# Main_schem.net
KiCad netlist of a schematic drawn in Altium Designer
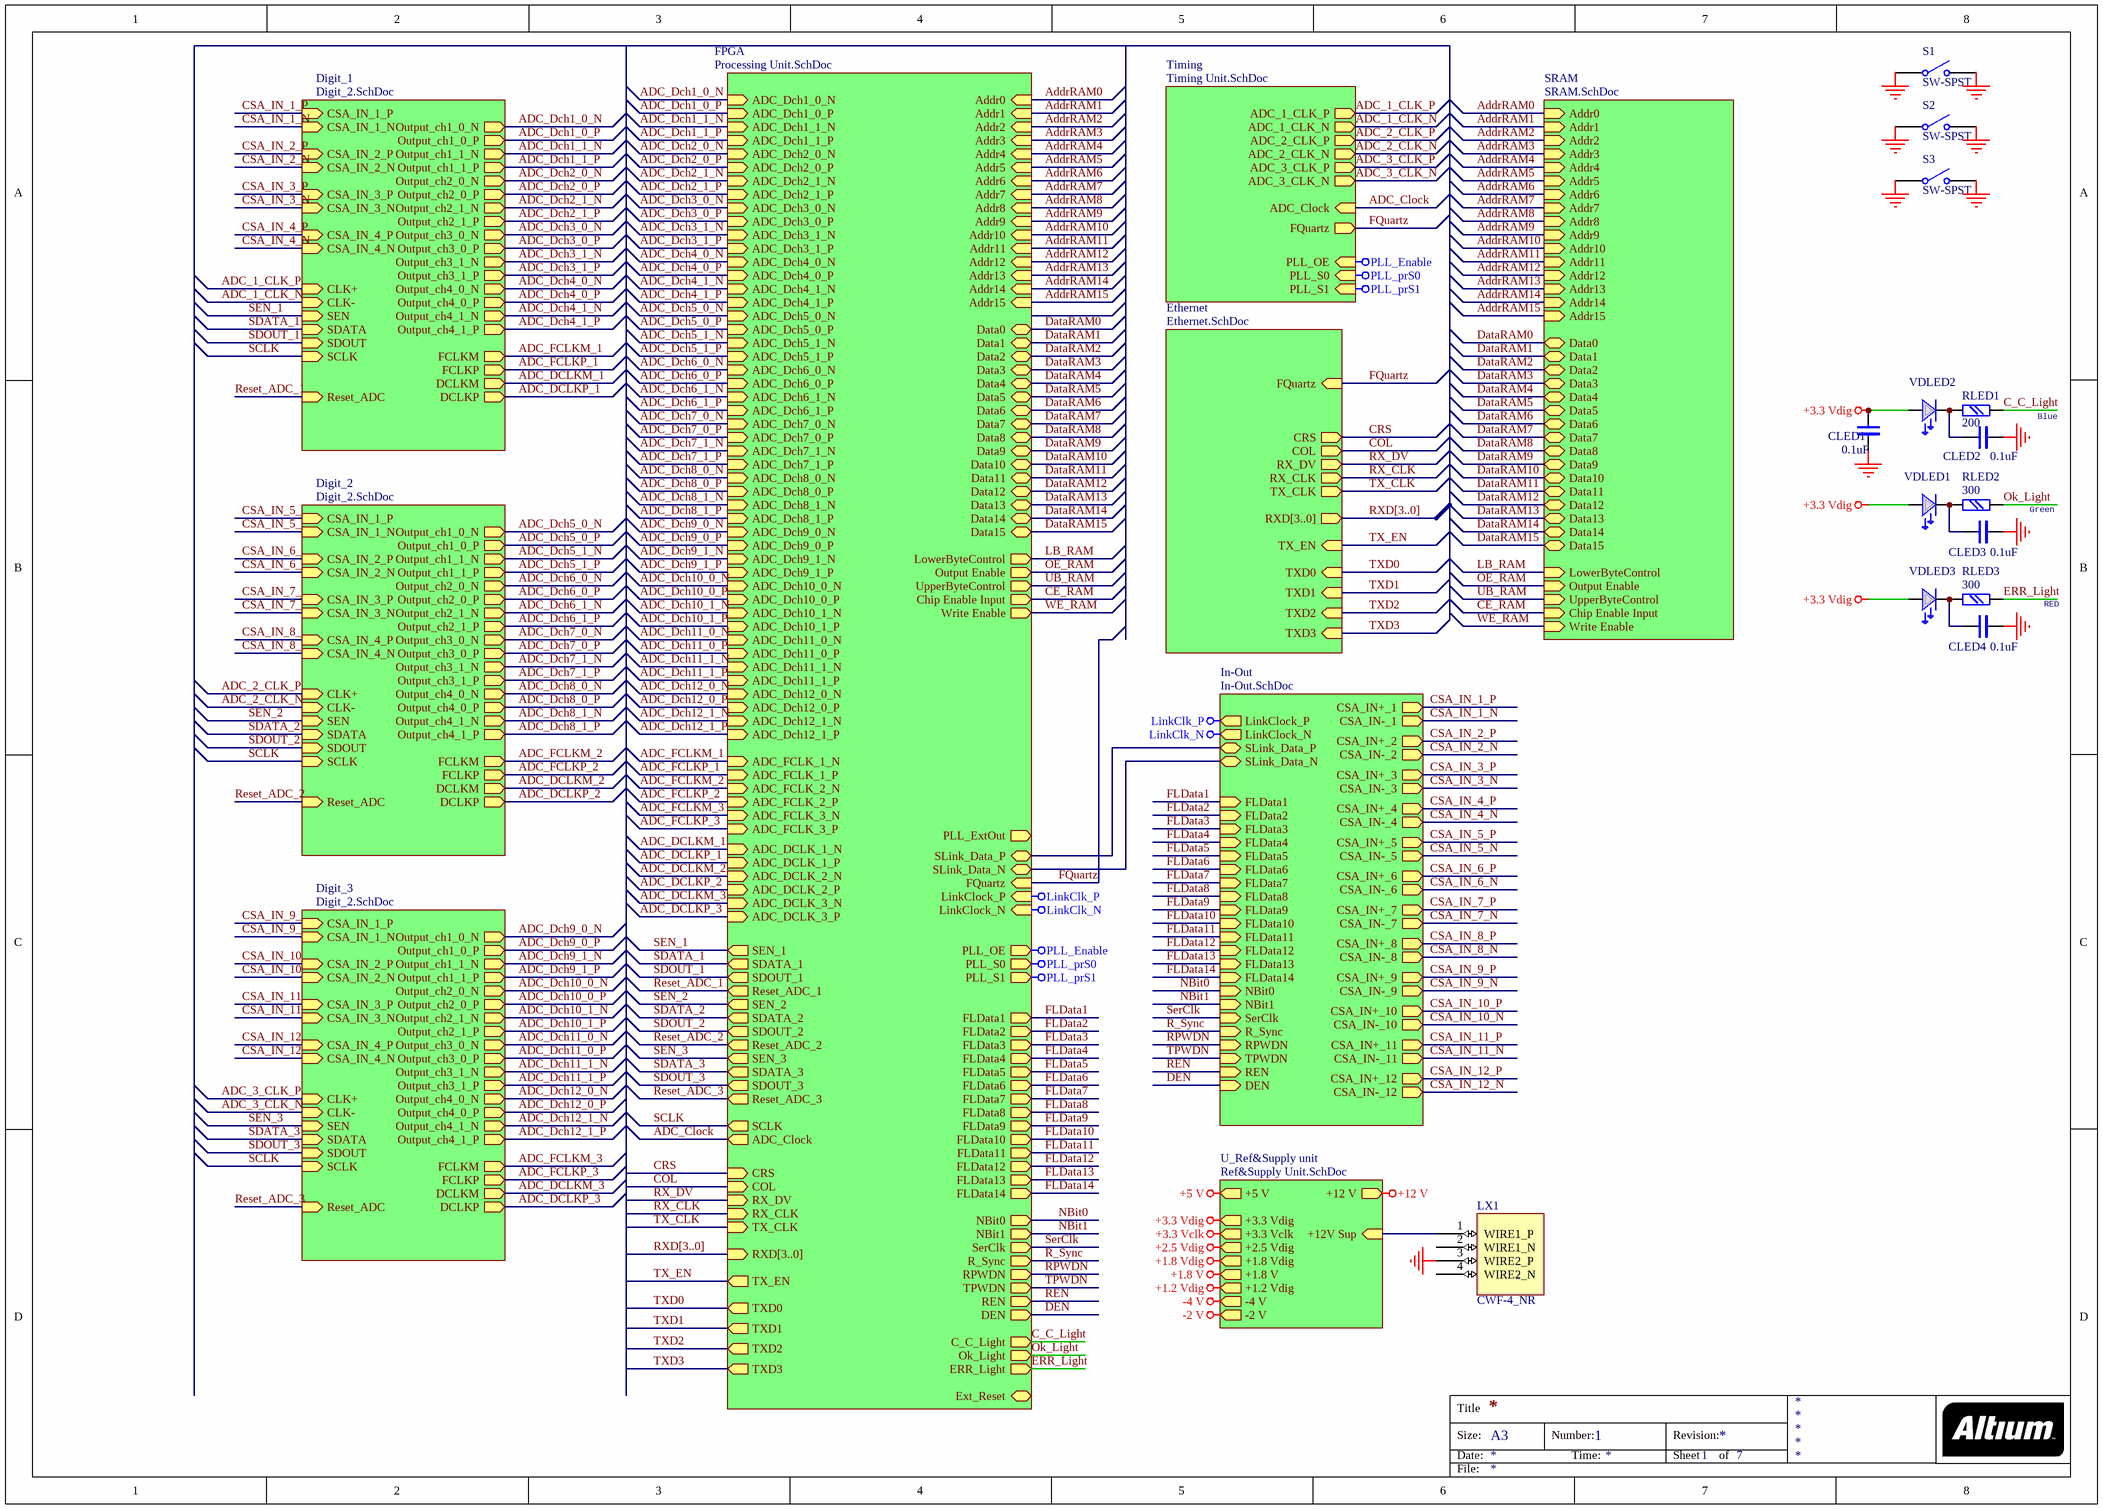
[diagram p0: Main schem.SchDoc]

(export (version "E")
  (design (tool "Eeschema 10.0.6"))
  (components
    (comp (ref "CLED1") (value "0.1uF") (footprint "chip0805") (libsource (lib "*") (part "C")))
    (comp (ref "CLED2") (value "0.1uF") (footprint "chip0603") (libsource (lib "*") (part "C")))
    (comp (ref "CLED3") (value "0.1uF") (footprint "chip0603") (libsource (lib "*") (part "C")))
    (comp (ref "CLED4") (value "0.1uF") (footprint "chip0603") (libsource (lib "*") (part "C")))
    (comp (ref "LX1") (value "CWF-4_NR") (footprint "CWF-4R") (libsource (lib "LXe_new") (part "CWF-4-R")))
    (comp (ref "RLED1") (value "200") (footprint "chip0603") (libsource (lib "*") (part "R")))
    (comp (ref "RLED2") (value "300") (footprint "chip0603") (libsource (lib "*") (part "R")))
    (comp (ref "RLED3") (value "300") (footprint "chip0603") (libsource (lib "*") (part "R")))
    (comp (ref "S1")
      (value "SW-SPST")
      (footprint "SPST-2")
      (description "Single-Pole, Single-Throw Switch")
      (fields (field (name "PUBLISHER") "Altium Limited"))
      (libsource (lib "Miscellaneous Devices") (part "SW-SPST"))
    )
    (comp (ref "S2")
      (value "SW-SPST")
      (footprint "SPST-2")
      (description "Single-Pole, Single-Throw Switch")
      (fields (field (name "PUBLISHER") "Altium Limited"))
      (libsource (lib "Miscellaneous Devices") (part "SW-SPST"))
    )
    (comp (ref "S3")
      (value "SW-SPST")
      (footprint "SPST-2")
      (description "Single-Pole, Single-Throw Switch")
      (fields (field (name "PUBLISHER") "Altium Limited"))
      (libsource (lib "Miscellaneous Devices") (part "SW-SPST"))
    )
    (comp (ref "VDLED1") (value "LED") (footprint "LED0805") (libsource (lib "*") (part "AL307")))
    (comp (ref "VDLED2") (value "LED") (footprint "LED1206") (libsource (lib "*") (part "AL307")))
    (comp (ref "VDLED3") (value "LED") (footprint "LED1206") (libsource (lib "*") (part "AL307")))
  )
  (nets
    (net (code "10") (name "+3.3 Vdig") (class "Default")
      (node (ref "CLED1") (pin "1") (pinfunction "1_1") (pintype "passive"))
      (node (ref "VDLED1") (pin "ANOD") (pinfunction "ANOD_ANOD") (pintype "passive"))
      (node (ref "VDLED2") (pin "ANOD") (pinfunction "ANOD_ANOD") (pintype "passive"))
      (node (ref "VDLED3") (pin "ANOD") (pinfunction "ANOD_ANOD") (pintype "passive"))
    )
    (net (code "15") (name "/+12V Sup") (class "Default")
      (node (ref "LX1") (pin "1") (pinfunction "WIRE1_P_1") (pintype "bidirectional"))
    )
    (net (code "126") (name "/C_C_Light") (class "Default")
      (node (ref "RLED1") (pin "2") (pinfunction "2_2") (pintype "passive"))
    )
    (net (code "144") (name "/ERR_Light") (class "Default")
      (node (ref "RLED3") (pin "2") (pinfunction "2_2") (pintype "passive"))
    )
    (net (code "165") (name "/Ok_Light") (class "Default")
      (node (ref "RLED2") (pin "2") (pinfunction "2_2") (pintype "passive"))
    )
    (net (code "198") (name "GND") (class "Default")
      (node (ref "CLED1") (pin "2") (pinfunction "2_2") (pintype "passive"))
      (node (ref "CLED2") (pin "2") (pinfunction "2_2") (pintype "passive"))
      (node (ref "CLED3") (pin "2") (pinfunction "2_2") (pintype "passive"))
      (node (ref "CLED4") (pin "2") (pinfunction "2_2") (pintype "passive"))
      (node (ref "LX1") (pin "3") (pinfunction "WIRE2_P_3") (pintype "bidirectional"))
      (node (ref "S1") (pin "1") (pinfunction "COMMON_1") (pintype "passive"))
      (node (ref "S1") (pin "2") (pinfunction "NO_2") (pintype "passive"))
      (node (ref "S2") (pin "1") (pinfunction "COMMON_1") (pintype "passive"))
      (node (ref "S2") (pin "2") (pinfunction "NO_2") (pintype "passive"))
      (node (ref "S3") (pin "1") (pinfunction "COMMON_1") (pintype "passive"))
      (node (ref "S3") (pin "2") (pinfunction "NO_2") (pintype "passive"))
    )
    (net (code "201") (name "Net-(CLED2-Pad1)") (class "Default")
      (node (ref "CLED2") (pin "1") (pinfunction "1_1") (pintype "passive"))
      (node (ref "RLED1") (pin "1") (pinfunction "1_1") (pintype "passive"))
      (node (ref "VDLED2") (pin "CATH") (pinfunction "CATH_CATH") (pintype "passive"))
    )
    (net (code "202") (name "Net-(CLED3-Pad1)") (class "Default")
      (node (ref "CLED3") (pin "1") (pinfunction "1_1") (pintype "passive"))
      (node (ref "RLED2") (pin "1") (pinfunction "1_1") (pintype "passive"))
      (node (ref "VDLED1") (pin "CATH") (pinfunction "CATH_CATH") (pintype "passive"))
    )
    (net (code "203") (name "Net-(CLED4-Pad1)") (class "Default")
      (node (ref "CLED4") (pin "1") (pinfunction "1_1") (pintype "passive"))
      (node (ref "RLED3") (pin "1") (pinfunction "1_1") (pintype "passive"))
      (node (ref "VDLED3") (pin "CATH") (pinfunction "CATH_CATH") (pintype "passive"))
    )
    (net (code "207") (name "unconnected-(LX1-WIRE1_N-Pad2)") (class "Default")
      (node (ref "LX1") (pin "2") (pinfunction "WIRE1_N_2") (pintype "bidirectional"))
    )
    (net (code "208") (name "unconnected-(LX1-WIRE2_N-Pad4)") (class "Default")
      (node (ref "LX1") (pin "4") (pinfunction "WIRE2_N_4") (pintype "bidirectional"))
    )
  )
)
